# AudioAmp.net
KiCad netlist of a schematic drawn in Altium Designer
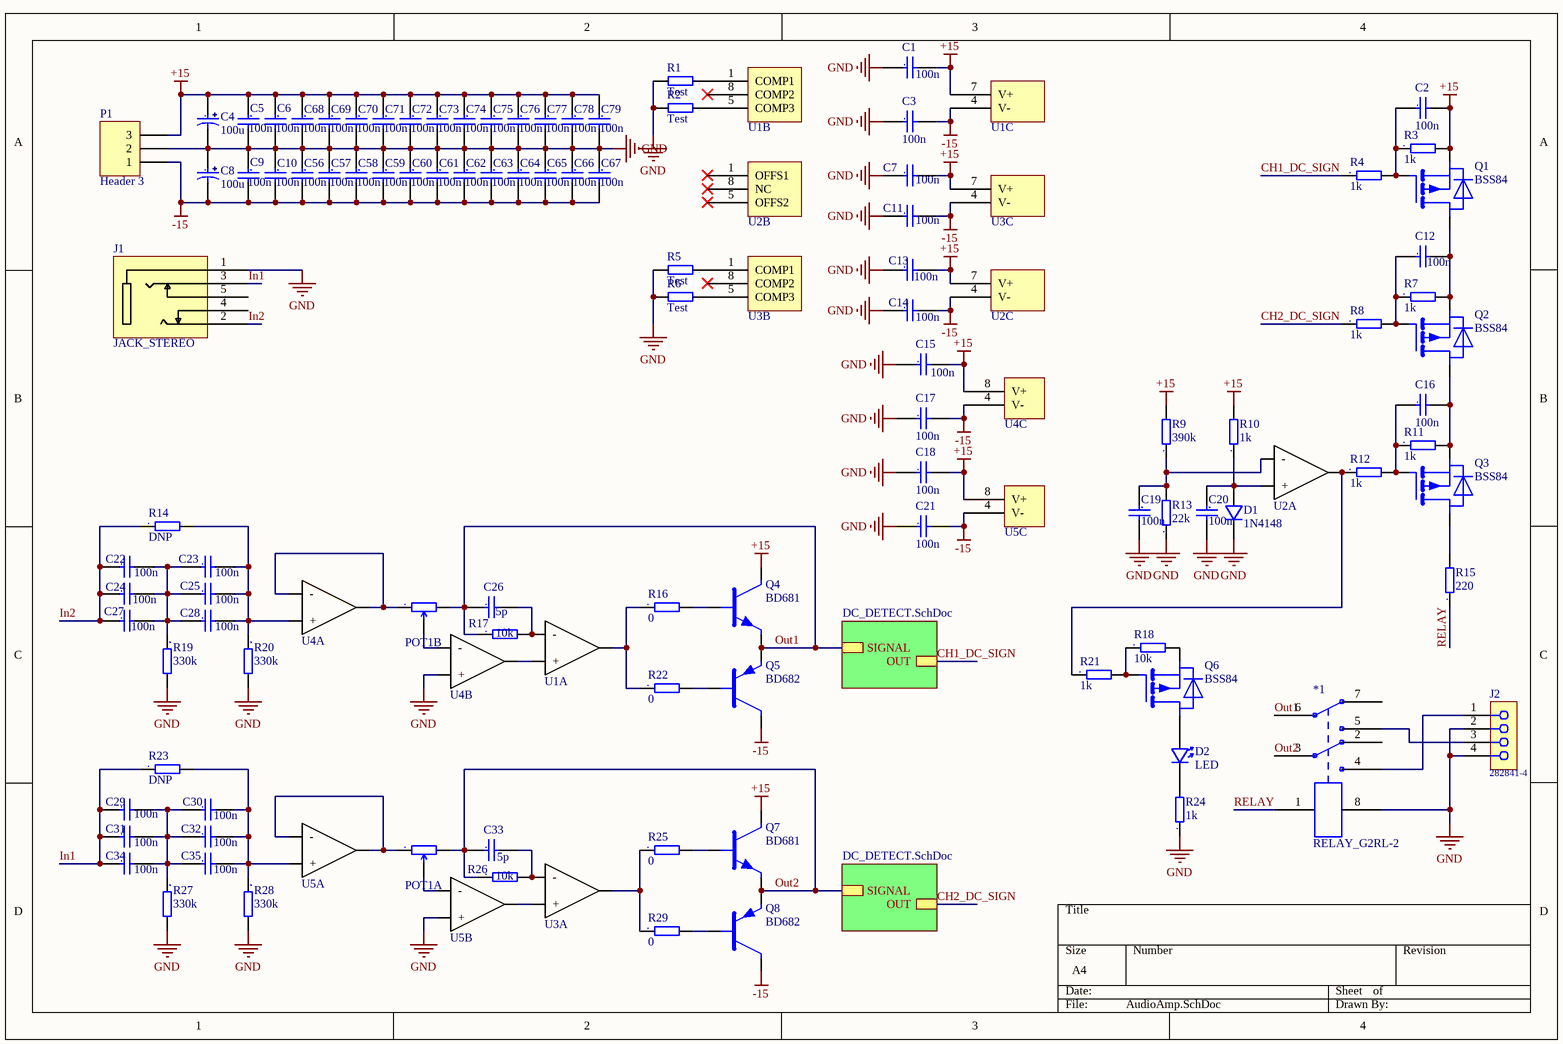
[diagram p0: AudioAmp.SchDoc]

(export (version "E")
  (design (tool "Eeschema 10.0.6"))
  (components
    (comp (ref "*1")
      (value "RELAY_G2RL-2")
      (footprint "G2RL-2")
      (libsource (lib "MyLib") (part "RELAY_G2RL-2"))
    )
    (comp (ref "C1") (value "100n") (footprint "C0603_N") (libsource (lib "MyLib") (part "CAP")))
    (comp (ref "C2") (value "100n") (footprint "C0603_N") (libsource (lib "MyLib") (part "CAP")))
    (comp (ref "C3") (value "100n") (footprint "C0603_N") (libsource (lib "MyLib") (part "CAP")))
    (comp (ref "C4") (value "100u") (footprint "C_TR3D") (libsource (lib "MyLib") (part "CAP_POL")))
    (comp (ref "C5") (value "100n") (footprint "C0603_N") (libsource (lib "MyLib") (part "CAP")))
    (comp (ref "C6") (value "100n") (footprint "C0603_N") (libsource (lib "MyLib") (part "CAP")))
    (comp (ref "C7") (value "100n") (footprint "C0603_N") (libsource (lib "MyLib") (part "CAP")))
    (comp (ref "C8") (value "100u") (footprint "C_TR3D") (libsource (lib "MyLib") (part "CAP_POL")))
    (comp (ref "C9") (value "100n") (footprint "C0603_N") (libsource (lib "MyLib") (part "CAP")))
    (comp (ref "C10") (value "100n") (footprint "C0603_N") (libsource (lib "MyLib") (part "CAP")))
    (comp (ref "C11") (value "100n") (footprint "C0603_N") (libsource (lib "MyLib") (part "CAP")))
    (comp (ref "C12") (value "100n") (footprint "C0603_N") (libsource (lib "MyLib") (part "CAP")))
    (comp (ref "C13") (value "100n") (footprint "C0603_N") (libsource (lib "MyLib") (part "CAP")))
    (comp (ref "C14") (value "100n") (footprint "C0603_N") (libsource (lib "MyLib") (part "CAP")))
    (comp (ref "C15") (value "100n") (footprint "C0603_N") (libsource (lib "MyLib") (part "CAP")))
    (comp (ref "C16") (value "100n") (footprint "C0603_N") (libsource (lib "MyLib") (part "CAP")))
    (comp (ref "C17") (value "100n") (footprint "C0603_N") (libsource (lib "MyLib") (part "CAP")))
    (comp (ref "C18") (value "100n") (footprint "C0603_N") (libsource (lib "MyLib") (part "CAP")))
    (comp (ref "C19") (value "100n") (footprint "C0603_N") (libsource (lib "MyLib") (part "CAP")))
    (comp (ref "C20") (value "100n") (footprint "C0603_N") (libsource (lib "MyLib") (part "CAP")))
    (comp (ref "C21") (value "100n") (footprint "C0603_N") (libsource (lib "MyLib") (part "CAP")))
    (comp (ref "C22") (value "100n") (footprint "C0603_N") (libsource (lib "MyLib") (part "CAP")))
    (comp (ref "C23") (value "100n") (footprint "C0603_N") (libsource (lib "MyLib") (part "CAP")))
    (comp (ref "C24") (value "100n") (footprint "C0603_N") (libsource (lib "MyLib") (part "CAP")))
    (comp (ref "C25") (value "100n") (footprint "C0603_N") (libsource (lib "MyLib") (part "CAP")))
    (comp (ref "C26") (value "5p") (footprint "C0603_N") (libsource (lib "MyLib") (part "CAP")))
    (comp (ref "C27") (value "100n") (footprint "C0603_N") (libsource (lib "MyLib") (part "CAP")))
    (comp (ref "C28") (value "100n") (footprint "C0603_N") (libsource (lib "MyLib") (part "CAP")))
    (comp (ref "C29") (value "100n") (footprint "C0603_N") (libsource (lib "MyLib") (part "CAP")))
    (comp (ref "C30") (value "100n") (footprint "C0603_N") (libsource (lib "MyLib") (part "CAP")))
    (comp (ref "C31") (value "100n") (footprint "C0603_N") (libsource (lib "MyLib") (part "CAP")))
    (comp (ref "C32") (value "100n") (footprint "C0603_N") (libsource (lib "MyLib") (part "CAP")))
    (comp (ref "C33") (value "5p") (footprint "C0603_N") (libsource (lib "MyLib") (part "CAP")))
    (comp (ref "C34") (value "100n") (footprint "C0603_N") (libsource (lib "MyLib") (part "CAP")))
    (comp (ref "C35") (value "100n") (footprint "C0603_N") (libsource (lib "MyLib") (part "CAP")))
    (comp (ref "C56") (value "100n") (footprint "C0603_N") (libsource (lib "MyLib") (part "CAP")))
    (comp (ref "C57") (value "100n") (footprint "C0603_N") (libsource (lib "MyLib") (part "CAP")))
    (comp (ref "C58") (value "100n") (footprint "C0603_N") (libsource (lib "MyLib") (part "CAP")))
    (comp (ref "C59") (value "100n") (footprint "C0603_N") (libsource (lib "MyLib") (part "CAP")))
    (comp (ref "C60") (value "100n") (footprint "C0603_N") (libsource (lib "MyLib") (part "CAP")))
    (comp (ref "C61") (value "100n") (footprint "C0603_N") (libsource (lib "MyLib") (part "CAP")))
    (comp (ref "C62") (value "100n") (footprint "C0603_N") (libsource (lib "MyLib") (part "CAP")))
    (comp (ref "C63") (value "100n") (footprint "C0603_N") (libsource (lib "MyLib") (part "CAP")))
    (comp (ref "C64") (value "100n") (footprint "C0603_N") (libsource (lib "MyLib") (part "CAP")))
    (comp (ref "C65") (value "100n") (footprint "C0603_N") (libsource (lib "MyLib") (part "CAP")))
    (comp (ref "C66") (value "100n") (footprint "C0603_N") (libsource (lib "MyLib") (part "CAP")))
    (comp (ref "C67") (value "100n") (footprint "C0603_N") (libsource (lib "MyLib") (part "CAP")))
    (comp (ref "C68") (value "100n") (footprint "C0603_N") (libsource (lib "MyLib") (part "CAP")))
    (comp (ref "C69") (value "100n") (footprint "C0603_N") (libsource (lib "MyLib") (part "CAP")))
    (comp (ref "C70") (value "100n") (footprint "C0603_N") (libsource (lib "MyLib") (part "CAP")))
    (comp (ref "C71") (value "100n") (footprint "C0603_N") (libsource (lib "MyLib") (part "CAP")))
    (comp (ref "C72") (value "100n") (footprint "C0603_N") (libsource (lib "MyLib") (part "CAP")))
    (comp (ref "C73") (value "100n") (footprint "C0603_N") (libsource (lib "MyLib") (part "CAP")))
    (comp (ref "C74") (value "100n") (footprint "C0603_N") (libsource (lib "MyLib") (part "CAP")))
    (comp (ref "C75") (value "100n") (footprint "C0603_N") (libsource (lib "MyLib") (part "CAP")))
    (comp (ref "C76") (value "100n") (footprint "C0603_N") (libsource (lib "MyLib") (part "CAP")))
    (comp (ref "C77") (value "100n") (footprint "C0603_N") (libsource (lib "MyLib") (part "CAP")))
    (comp (ref "C78") (value "100n") (footprint "C0603_N") (libsource (lib "MyLib") (part "CAP")))
    (comp (ref "C79") (value "100n") (footprint "C0603_N") (libsource (lib "MyLib") (part "CAP")))
    (comp (ref "D1") (value "1N4148") (footprint "SOD-80") (libsource (lib "MyLib") (part "DIODE")))
    (comp (ref "D2") (value "LED") (footprint "LED_3mm") (libsource (lib "MyLib") (part "LED")))
    (comp (ref "J1")
      (value "JACK_STEREO")
      (footprint "1503 09")
      (description "3,5mm Stereo Jack connector, Lumberg 1503 09 type")
      (libsource (lib "MyLib") (part "JACK_STEREO"))
    )
    (comp (ref "J2")
      (value "282841-4")
      (footprint "TERM_BLOCK_4x1")
      (description "Socket")
      (libsource (lib "MyLib") (part "SOCHDR_4X1"))
    )
    (comp (ref "P1")
      (value "Header 3")
      (footprint "HDR1X3")
      (description "Header, 3-Pin")
      (fields (field (name "PUBLISHER") "Altium Limited"))
      (libsource (lib "Miscellaneous Connectors") (part "Header 3"))
    )
    (comp (ref "POT1")
      (value "RES_POT_S")
      (footprint "POT_STEREO")
      (description "Stereo")
      (libsource (lib "MyLib") (part "RES_POT_S"))
    )
    (comp (ref "Q1") (value "BSS84") (footprint "SOT23_123_N") (libsource (lib "MyLib") (part "MOSFET_P")))
    (comp (ref "Q2") (value "BSS84") (footprint "SOT23_123_N") (libsource (lib "MyLib") (part "MOSFET_P")))
    (comp (ref "Q3") (value "BSS84") (footprint "SOT23_123_N") (libsource (lib "MyLib") (part "MOSFET_P")))
    (comp (ref "Q4") (value "BD681") (footprint "TO-126") (libsource (lib "MyLib") (part "BJT_NPN")))
    (comp (ref "Q5") (value "BD682") (footprint "TO-126") (libsource (lib "MyLib") (part "BJT_PNP")))
    (comp (ref "Q6") (value "BSS84") (footprint "SOT23_123_N") (libsource (lib "MyLib") (part "MOSFET_P")))
    (comp (ref "Q7") (value "BD681") (footprint "TO-126") (libsource (lib "MyLib") (part "BJT_NPN")))
    (comp (ref "Q8") (value "BD682") (footprint "TO-126") (libsource (lib "MyLib") (part "BJT_PNP")))
    (comp (ref "R1") (value "Test") (footprint "R0603_N") (libsource (lib "MyLib") (part "RES")))
    (comp (ref "R2") (value "Test") (footprint "R0603_N") (libsource (lib "MyLib") (part "RES")))
    (comp (ref "R3") (value "1k") (footprint "R0603_N") (libsource (lib "MyLib") (part "RES")))
    (comp (ref "R4") (value "1k") (footprint "R0603_N") (libsource (lib "MyLib") (part "RES")))
    (comp (ref "R5") (value "Test") (footprint "R0603_N") (libsource (lib "MyLib") (part "RES")))
    (comp (ref "R6") (value "Test") (footprint "R0603_N") (libsource (lib "MyLib") (part "RES")))
    (comp (ref "R7") (value "1k") (footprint "R0603_N") (libsource (lib "MyLib") (part "RES")))
    (comp (ref "R8") (value "1k") (footprint "R0603_N") (libsource (lib "MyLib") (part "RES")))
    (comp (ref "R9") (value "390k") (footprint "R0603_N") (libsource (lib "MyLib") (part "RES")))
    (comp (ref "R10") (value "1k") (footprint "R0603_N") (libsource (lib "MyLib") (part "RES")))
    (comp (ref "R11") (value "1k") (footprint "R0603_N") (libsource (lib "MyLib") (part "RES")))
    (comp (ref "R12") (value "1k") (footprint "R0603_N") (libsource (lib "MyLib") (part "RES")))
    (comp (ref "R13") (value "22k") (footprint "R0603_N") (libsource (lib "MyLib") (part "RES")))
    (comp (ref "R14") (value "DNP") (footprint "R0603_N") (libsource (lib "MyLib") (part "RES")))
    (comp (ref "R15") (value "220") (footprint "R0603_N") (libsource (lib "MyLib") (part "RES")))
    (comp (ref "R16") (value "0") (footprint "R0603_N") (libsource (lib "MyLib") (part "RES")))
    (comp (ref "R17") (value "10k") (footprint "R0603_N") (libsource (lib "MyLib") (part "RES")))
    (comp (ref "R18") (value "10k") (footprint "R0603_N") (libsource (lib "MyLib") (part "RES")))
    (comp (ref "R19") (value "330k") (footprint "R0603_N") (libsource (lib "MyLib") (part "RES")))
    (comp (ref "R20") (value "330k") (footprint "R0603_N") (libsource (lib "MyLib") (part "RES")))
    (comp (ref "R21") (value "1k") (footprint "R0603_N") (libsource (lib "MyLib") (part "RES")))
    (comp (ref "R22") (value "0") (footprint "R0603_N") (libsource (lib "MyLib") (part "RES")))
    (comp (ref "R23") (value "DNP") (footprint "R0603_N") (libsource (lib "MyLib") (part "RES")))
    (comp (ref "R24") (value "1k") (footprint "R0603_N") (libsource (lib "MyLib") (part "RES")))
    (comp (ref "R25") (value "0") (footprint "R0603_N") (libsource (lib "MyLib") (part "RES")))
    (comp (ref "R26") (value "10k") (footprint "R0603_N") (libsource (lib "MyLib") (part "RES")))
    (comp (ref "R27") (value "330k") (footprint "R0603_N") (libsource (lib "MyLib") (part "RES")))
    (comp (ref "R28") (value "330k") (footprint "R0603_N") (libsource (lib "MyLib") (part "RES")))
    (comp (ref "R29") (value "0") (footprint "R0603_N") (libsource (lib "MyLib") (part "RES")))
    (comp (ref "U1") (value "LM318") (footprint "SOIC-8") (libsource (lib "MyLib") (part "LM318")))
    (comp (ref "U2") (value "uA741") (footprint "SOIC-8") (libsource (lib "MyLib") (part "uA741")))
    (comp (ref "U3") (value "LM318") (footprint "SOIC-8") (libsource (lib "MyLib") (part "LM318")))
    (comp (ref "U4")
      (value "TL072")
      (footprint "SOIC-8")
      (description "Dual op. amp.")
      (libsource (lib "MyLib") (part "TL072"))
    )
    (comp (ref "U5")
      (value "TL072")
      (footprint "SOIC-8")
      (description "Dual op. amp.")
      (libsource (lib "MyLib") (part "TL072"))
    )
  )
  (nets
    (net (code "1") (name "+15") (class "Default")
      (node (ref "C1") (pin "2") (pinfunction "2_2") (pintype "passive"))
      (node (ref "C13") (pin "2") (pinfunction "2_2") (pintype "passive"))
      (node (ref "C15") (pin "2") (pinfunction "2_2") (pintype "passive"))
      (node (ref "C18") (pin "2") (pinfunction "2_2") (pintype "passive"))
      (node (ref "C2") (pin "2") (pinfunction "2_2") (pintype "passive"))
      (node (ref "C4") (pin "P") (pinfunction "P_P") (pintype "passive"))
      (node (ref "C5") (pin "1") (pinfunction "1_1") (pintype "passive"))
      (node (ref "C6") (pin "1") (pinfunction "1_1") (pintype "passive"))
      (node (ref "C68") (pin "1") (pinfunction "1_1") (pintype "passive"))
      (node (ref "C69") (pin "1") (pinfunction "1_1") (pintype "passive"))
      (node (ref "C7") (pin "2") (pinfunction "2_2") (pintype "passive"))
      (node (ref "C70") (pin "1") (pinfunction "1_1") (pintype "passive"))
      (node (ref "C71") (pin "1") (pinfunction "1_1") (pintype "passive"))
      (node (ref "C72") (pin "1") (pinfunction "1_1") (pintype "passive"))
      (node (ref "C73") (pin "1") (pinfunction "1_1") (pintype "passive"))
      (node (ref "C74") (pin "1") (pinfunction "1_1") (pintype "passive"))
      (node (ref "C75") (pin "1") (pinfunction "1_1") (pintype "passive"))
      (node (ref "C76") (pin "1") (pinfunction "1_1") (pintype "passive"))
      (node (ref "C77") (pin "1") (pinfunction "1_1") (pintype "passive"))
      (node (ref "C78") (pin "1") (pinfunction "1_1") (pintype "passive"))
      (node (ref "C79") (pin "1") (pinfunction "1_1") (pintype "passive"))
      (node (ref "P1") (pin "3") (pinfunction "3_3") (pintype "passive"))
      (node (ref "Q1") (pin "S") (pinfunction "S_S") (pintype "passive"))
      (node (ref "Q4") (pin "C") (pinfunction "C_C") (pintype "passive"))
      (node (ref "Q7") (pin "C") (pinfunction "C_C") (pintype "passive"))
      (node (ref "R10") (pin "2") (pinfunction "2_2") (pintype "passive"))
      (node (ref "R3") (pin "2") (pinfunction "2_2") (pintype "passive"))
      (node (ref "R9") (pin "2") (pinfunction "2_2") (pintype "passive"))
      (node (ref "U1") (pin "7") (pinfunction "V+_7") (pintype "passive"))
      (node (ref "U2") (pin "7") (pinfunction "V+_7") (pintype "passive"))
      (node (ref "U3") (pin "7") (pinfunction "V+_7") (pintype "passive"))
      (node (ref "U4") (pin "8") (pinfunction "V+_8") (pintype "passive"))
      (node (ref "U5") (pin "8") (pinfunction "V+_8") (pintype "passive"))
    )
    (net (code "2") (name "-15") (class "Default")
      (node (ref "C10") (pin "2") (pinfunction "2_2") (pintype "passive"))
      (node (ref "C11") (pin "2") (pinfunction "2_2") (pintype "passive"))
      (node (ref "C14") (pin "2") (pinfunction "2_2") (pintype "passive"))
      (node (ref "C17") (pin "2") (pinfunction "2_2") (pintype "passive"))
      (node (ref "C21") (pin "2") (pinfunction "2_2") (pintype "passive"))
      (node (ref "C3") (pin "2") (pinfunction "2_2") (pintype "passive"))
      (node (ref "C56") (pin "2") (pinfunction "2_2") (pintype "passive"))
      (node (ref "C57") (pin "2") (pinfunction "2_2") (pintype "passive"))
      (node (ref "C58") (pin "2") (pinfunction "2_2") (pintype "passive"))
      (node (ref "C59") (pin "2") (pinfunction "2_2") (pintype "passive"))
      (node (ref "C60") (pin "2") (pinfunction "2_2") (pintype "passive"))
      (node (ref "C61") (pin "2") (pinfunction "2_2") (pintype "passive"))
      (node (ref "C62") (pin "2") (pinfunction "2_2") (pintype "passive"))
      (node (ref "C63") (pin "2") (pinfunction "2_2") (pintype "passive"))
      (node (ref "C64") (pin "2") (pinfunction "2_2") (pintype "passive"))
      (node (ref "C65") (pin "2") (pinfunction "2_2") (pintype "passive"))
      (node (ref "C66") (pin "2") (pinfunction "2_2") (pintype "passive"))
      (node (ref "C67") (pin "2") (pinfunction "2_2") (pintype "passive"))
      (node (ref "C8") (pin "N") (pinfunction "N_N") (pintype "passive"))
      (node (ref "C9") (pin "2") (pinfunction "2_2") (pintype "passive"))
      (node (ref "P1") (pin "1") (pinfunction "1_1") (pintype "passive"))
      (node (ref "Q5") (pin "C") (pinfunction "C_C") (pintype "passive"))
      (node (ref "Q8") (pin "C") (pinfunction "C_C") (pintype "passive"))
      (node (ref "U1") (pin "4") (pinfunction "V-_4") (pintype "passive"))
      (node (ref "U2") (pin "4") (pinfunction "V-_4") (pintype "passive"))
      (node (ref "U3") (pin "4") (pinfunction "V-_4") (pintype "passive"))
      (node (ref "U4") (pin "4") (pinfunction "V-_4") (pintype "passive"))
      (node (ref "U5") (pin "4") (pinfunction "V-_4") (pintype "passive"))
    )
    (net (code "3") (name "/CH1_DC_SIGN") (class "Default")
      (node (ref "R4") (pin "1") (pinfunction "1_1") (pintype "passive"))
    )
    (net (code "4") (name "/CH2_DC_SIGN") (class "Default")
      (node (ref "R8") (pin "1") (pinfunction "1_1") (pintype "passive"))
    )
    (net (code "5") (name "/In1") (class "Default")
      (node (ref "C29") (pin "1") (pinfunction "1_1") (pintype "passive"))
      (node (ref "C31") (pin "1") (pinfunction "1_1") (pintype "passive"))
      (node (ref "C34") (pin "1") (pinfunction "1_1") (pintype "passive"))
      (node (ref "J1") (pin "3") (pintype "passive"))
      (node (ref "R23") (pin "1") (pinfunction "1_1") (pintype "passive"))
    )
    (net (code "6") (name "/In2") (class "Default")
      (node (ref "C22") (pin "1") (pinfunction "1_1") (pintype "passive"))
      (node (ref "C24") (pin "1") (pinfunction "1_1") (pintype "passive"))
      (node (ref "C27") (pin "1") (pinfunction "1_1") (pintype "passive"))
      (node (ref "J1") (pin "2") (pintype "passive"))
      (node (ref "R14") (pin "1") (pinfunction "1_1") (pintype "passive"))
    )
    (net (code "7") (name "/Out1") (class "Default")
      (node (ref "*1") (pin "6") (pintype "passive"))
      (node (ref "C26") (pin "1") (pinfunction "1_1") (pintype "passive"))
      (node (ref "POT1") (pin "6") (pinfunction "CW_6") (pintype "passive"))
      (node (ref "Q4") (pin "E") (pinfunction "E_E") (pintype "passive"))
      (node (ref "Q5") (pin "E") (pinfunction "E_E") (pintype "passive"))
      (node (ref "R17") (pin "1") (pinfunction "1_1") (pintype "passive"))
    )
    (net (code "8") (name "/Out2") (class "Default")
      (node (ref "*1") (pin "3") (pintype "passive"))
      (node (ref "C33") (pin "1") (pinfunction "1_1") (pintype "passive"))
      (node (ref "POT1") (pin "3") (pinfunction "CW_3") (pintype "passive"))
      (node (ref "Q7") (pin "E") (pinfunction "E_E") (pintype "passive"))
      (node (ref "Q8") (pin "E") (pinfunction "E_E") (pintype "passive"))
      (node (ref "R26") (pin "1") (pinfunction "1_1") (pintype "passive"))
    )
    (net (code "9") (name "/RELAY") (class "Default")
      (node (ref "*1") (pin "1") (pintype "passive"))
      (node (ref "R15") (pin "1") (pinfunction "1_1") (pintype "passive"))
    )
    (net (code "10") (name "GND") (class "Default")
      (node (ref "*1") (pin "8") (pintype "passive"))
      (node (ref "C1") (pin "1") (pinfunction "1_1") (pintype "passive"))
      (node (ref "C10") (pin "1") (pinfunction "1_1") (pintype "passive"))
      (node (ref "C11") (pin "1") (pinfunction "1_1") (pintype "passive"))
      (node (ref "C13") (pin "1") (pinfunction "1_1") (pintype "passive"))
      (node (ref "C14") (pin "1") (pinfunction "1_1") (pintype "passive"))
      (node (ref "C15") (pin "1") (pinfunction "1_1") (pintype "passive"))
      (node (ref "C17") (pin "1") (pinfunction "1_1") (pintype "passive"))
      (node (ref "C18") (pin "1") (pinfunction "1_1") (pintype "passive"))
      (node (ref "C19") (pin "2") (pinfunction "2_2") (pintype "passive"))
      (node (ref "C20") (pin "2") (pinfunction "2_2") (pintype "passive"))
      (node (ref "C21") (pin "1") (pinfunction "1_1") (pintype "passive"))
      (node (ref "C3") (pin "1") (pinfunction "1_1") (pintype "passive"))
      (node (ref "C4") (pin "N") (pinfunction "N_N") (pintype "passive"))
      (node (ref "C5") (pin "2") (pinfunction "2_2") (pintype "passive"))
      (node (ref "C56") (pin "1") (pinfunction "1_1") (pintype "passive"))
      (node (ref "C57") (pin "1") (pinfunction "1_1") (pintype "passive"))
      (node (ref "C58") (pin "1") (pinfunction "1_1") (pintype "passive"))
      (node (ref "C59") (pin "1") (pinfunction "1_1") (pintype "passive"))
      (node (ref "C6") (pin "2") (pinfunction "2_2") (pintype "passive"))
      (node (ref "C60") (pin "1") (pinfunction "1_1") (pintype "passive"))
      (node (ref "C61") (pin "1") (pinfunction "1_1") (pintype "passive"))
      (node (ref "C62") (pin "1") (pinfunction "1_1") (pintype "passive"))
      (node (ref "C63") (pin "1") (pinfunction "1_1") (pintype "passive"))
      (node (ref "C64") (pin "1") (pinfunction "1_1") (pintype "passive"))
      (node (ref "C65") (pin "1") (pinfunction "1_1") (pintype "passive"))
      (node (ref "C66") (pin "1") (pinfunction "1_1") (pintype "passive"))
      (node (ref "C67") (pin "1") (pinfunction "1_1") (pintype "passive"))
      (node (ref "C68") (pin "2") (pinfunction "2_2") (pintype "passive"))
      (node (ref "C69") (pin "2") (pinfunction "2_2") (pintype "passive"))
      (node (ref "C7") (pin "1") (pinfunction "1_1") (pintype "passive"))
      (node (ref "C70") (pin "2") (pinfunction "2_2") (pintype "passive"))
      (node (ref "C71") (pin "2") (pinfunction "2_2") (pintype "passive"))
      (node (ref "C72") (pin "2") (pinfunction "2_2") (pintype "passive"))
      (node (ref "C73") (pin "2") (pinfunction "2_2") (pintype "passive"))
      (node (ref "C74") (pin "2") (pinfunction "2_2") (pintype "passive"))
      (node (ref "C75") (pin "2") (pinfunction "2_2") (pintype "passive"))
      (node (ref "C76") (pin "2") (pinfunction "2_2") (pintype "passive"))
      (node (ref "C77") (pin "2") (pinfunction "2_2") (pintype "passive"))
      (node (ref "C78") (pin "2") (pinfunction "2_2") (pintype "passive"))
      (node (ref "C79") (pin "2") (pinfunction "2_2") (pintype "passive"))
      (node (ref "C8") (pin "P") (pinfunction "P_P") (pintype "passive"))
      (node (ref "C9") (pin "1") (pinfunction "1_1") (pintype "passive"))
      (node (ref "D1") (pin "C") (pinfunction "C_C") (pintype "passive"))
      (node (ref "J1") (pin "1") (pintype "passive"))
      (node (ref "J2") (pin "2") (pinfunction "2_2") (pintype "passive"))
      (node (ref "J2") (pin "4") (pinfunction "4_4") (pintype "passive"))
      (node (ref "P1") (pin "2") (pinfunction "2_2") (pintype "passive"))
      (node (ref "R1") (pin "2") (pinfunction "2_2") (pintype "passive"))
      (node (ref "R13") (pin "1") (pinfunction "1_1") (pintype "passive"))
      (node (ref "R19") (pin "2") (pinfunction "2_2") (pintype "passive"))
      (node (ref "R2") (pin "2") (pinfunction "2_2") (pintype "passive"))
      (node (ref "R20") (pin "2") (pinfunction "2_2") (pintype "passive"))
      (node (ref "R24") (pin "1") (pinfunction "1_1") (pintype "passive"))
      (node (ref "R27") (pin "2") (pinfunction "2_2") (pintype "passive"))
      (node (ref "R28") (pin "2") (pinfunction "2_2") (pintype "passive"))
      (node (ref "R5") (pin "2") (pinfunction "2_2") (pintype "passive"))
      (node (ref "R6") (pin "2") (pinfunction "2_2") (pintype "passive"))
      (node (ref "U4") (pin "5") (pinfunction "+_5") (pintype "passive"))
      (node (ref "U5") (pin "5") (pinfunction "+_5") (pintype "passive"))
    )
    (net (code "11") (name "Net-(*1-Pad4)") (class "Default")
      (node (ref "*1") (pin "4") (pintype "passive"))
      (node (ref "J2") (pin "1") (pinfunction "1_1") (pintype "passive"))
    )
    (net (code "12") (name "Net-(*1-Pad5)") (class "Default")
      (node (ref "*1") (pin "5") (pintype "passive"))
      (node (ref "J2") (pin "3") (pinfunction "3_3") (pintype "passive"))
    )
    (net (code "13") (name "Net-(C2-Pad1)") (class "Default")
      (node (ref "C2") (pin "1") (pinfunction "1_1") (pintype "passive"))
      (node (ref "Q1") (pin "G") (pinfunction "G_G") (pintype "passive"))
      (node (ref "R3") (pin "1") (pinfunction "1_1") (pintype "passive"))
      (node (ref "R4") (pin "2") (pinfunction "2_2") (pintype "passive"))
    )
    (net (code "14") (name "Net-(C12-Pad1)") (class "Default")
      (node (ref "C12") (pin "1") (pinfunction "1_1") (pintype "passive"))
      (node (ref "Q2") (pin "G") (pinfunction "G_G") (pintype "passive"))
      (node (ref "R7") (pin "1") (pinfunction "1_1") (pintype "passive"))
      (node (ref "R8") (pin "2") (pinfunction "2_2") (pintype "passive"))
    )
    (net (code "15") (name "Net-(C12-Pad2)") (class "Default")
      (node (ref "C12") (pin "2") (pinfunction "2_2") (pintype "passive"))
      (node (ref "Q1") (pin "D") (pinfunction "D_D") (pintype "passive"))
      (node (ref "Q2") (pin "S") (pinfunction "S_S") (pintype "passive"))
      (node (ref "R7") (pin "2") (pinfunction "2_2") (pintype "passive"))
    )
    (net (code "16") (name "Net-(C16-Pad1)") (class "Default")
      (node (ref "C16") (pin "1") (pinfunction "1_1") (pintype "passive"))
      (node (ref "Q3") (pin "G") (pinfunction "G_G") (pintype "passive"))
      (node (ref "R11") (pin "1") (pinfunction "1_1") (pintype "passive"))
      (node (ref "R12") (pin "2") (pinfunction "2_2") (pintype "passive"))
    )
    (net (code "17") (name "Net-(C16-Pad2)") (class "Default")
      (node (ref "C16") (pin "2") (pinfunction "2_2") (pintype "passive"))
      (node (ref "Q2") (pin "D") (pinfunction "D_D") (pintype "passive"))
      (node (ref "Q3") (pin "S") (pinfunction "S_S") (pintype "passive"))
      (node (ref "R11") (pin "2") (pinfunction "2_2") (pintype "passive"))
    )
    (net (code "18") (name "Net-(C22-Pad2)") (class "Default")
      (node (ref "C22") (pin "2") (pinfunction "2_2") (pintype "passive"))
      (node (ref "C23") (pin "1") (pinfunction "1_1") (pintype "passive"))
      (node (ref "C24") (pin "2") (pinfunction "2_2") (pintype "passive"))
      (node (ref "C25") (pin "1") (pinfunction "1_1") (pintype "passive"))
      (node (ref "C27") (pin "2") (pinfunction "2_2") (pintype "passive"))
      (node (ref "C28") (pin "1") (pinfunction "1_1") (pintype "passive"))
      (node (ref "R19") (pin "1") (pinfunction "1_1") (pintype "passive"))
    )
    (net (code "19") (name "Net-(C29-Pad2)") (class "Default")
      (node (ref "C29") (pin "2") (pinfunction "2_2") (pintype "passive"))
      (node (ref "C30") (pin "1") (pinfunction "1_1") (pintype "passive"))
      (node (ref "C31") (pin "2") (pinfunction "2_2") (pintype "passive"))
      (node (ref "C32") (pin "1") (pinfunction "1_1") (pintype "passive"))
      (node (ref "C34") (pin "2") (pinfunction "2_2") (pintype "passive"))
      (node (ref "C35") (pin "1") (pinfunction "1_1") (pintype "passive"))
      (node (ref "R27") (pin "1") (pinfunction "1_1") (pintype "passive"))
    )
    (net (code "20") (name "Net-(D2-PadA)") (class "Default")
      (node (ref "D2") (pin "A") (pinfunction "A_A") (pintype "passive"))
      (node (ref "Q6") (pin "D") (pinfunction "D_D") (pintype "passive"))
    )
    (net (code "21") (name "Net-(D2-PadK)") (class "Default")
      (node (ref "D2") (pin "K") (pinfunction "K_K") (pintype "passive"))
      (node (ref "R24") (pin "2") (pinfunction "2_2") (pintype "passive"))
    )
    (net (code "22") (name "Net-(POT1A-CCW)") (class "Default")
      (node (ref "POT1") (pin "1") (pinfunction "CCW_1") (pintype "passive"))
      (node (ref "U5") (pin "1") (pinfunction "Out_1") (pintype "passive"))
      (node (ref "U5") (pin "2") (pinfunction "-_2") (pintype "passive"))
    )
    (net (code "23") (name "Net-(POT1A-WIPER)") (class "Default")
      (node (ref "POT1") (pin "2") (pinfunction "WIPER_2") (pintype "passive"))
      (node (ref "U5") (pin "6") (pinfunction "-_6") (pintype "passive"))
    )
    (net (code "24") (name "Net-(POT1B-CCW)") (class "Default")
      (node (ref "POT1") (pin "4") (pinfunction "CCW_4") (pintype "passive"))
      (node (ref "U4") (pin "1") (pinfunction "Out_1") (pintype "passive"))
      (node (ref "U4") (pin "2") (pinfunction "-_2") (pintype "passive"))
    )
    (net (code "25") (name "Net-(POT1B-WIPER)") (class "Default")
      (node (ref "POT1") (pin "5") (pinfunction "WIPER_5") (pintype "passive"))
      (node (ref "U4") (pin "6") (pinfunction "-_6") (pintype "passive"))
    )
    (net (code "26") (name "Net-(Q3-PadD)") (class "Default")
      (node (ref "Q3") (pin "D") (pinfunction "D_D") (pintype "passive"))
      (node (ref "R15") (pin "2") (pinfunction "2_2") (pintype "passive"))
    )
    (net (code "27") (name "Net-(Q4-PadB)") (class "Default")
      (node (ref "Q4") (pin "B") (pinfunction "B_B") (pintype "passive"))
      (node (ref "R16") (pin "2") (pinfunction "2_2") (pintype "passive"))
    )
    (net (code "28") (name "Net-(Q5-PadB)") (class "Default")
      (node (ref "Q5") (pin "B") (pinfunction "B_B") (pintype "passive"))
      (node (ref "R22") (pin "2") (pinfunction "2_2") (pintype "passive"))
    )
    (net (code "29") (name "Net-(Q6-PadG)") (class "Default")
      (node (ref "Q6") (pin "G") (pinfunction "G_G") (pintype "passive"))
      (node (ref "R18") (pin "1") (pinfunction "1_1") (pintype "passive"))
      (node (ref "R21") (pin "2") (pinfunction "2_2") (pintype "passive"))
    )
    (net (code "30") (name "Net-(Q6-PadS)") (class "Default")
      (node (ref "Q6") (pin "S") (pinfunction "S_S") (pintype "passive"))
      (node (ref "R18") (pin "2") (pinfunction "2_2") (pintype "passive"))
    )
    (net (code "31") (name "Net-(Q7-PadB)") (class "Default")
      (node (ref "Q7") (pin "B") (pinfunction "B_B") (pintype "passive"))
      (node (ref "R25") (pin "2") (pinfunction "2_2") (pintype "passive"))
    )
    (net (code "32") (name "Net-(Q8-PadB)") (class "Default")
      (node (ref "Q8") (pin "B") (pinfunction "B_B") (pintype "passive"))
      (node (ref "R29") (pin "2") (pinfunction "2_2") (pintype "passive"))
    )
    (net (code "33") (name "Net-(U1A-+)") (class "Default")
      (node (ref "U1") (pin "3") (pinfunction "+_3") (pintype "passive"))
      (node (ref "U4") (pin "7") (pinfunction "Out_7") (pintype "passive"))
    )
    (net (code "34") (name "Net-(U1A--)") (class "Default")
      (node (ref "C26") (pin "2") (pinfunction "2_2") (pintype "passive"))
      (node (ref "R17") (pin "2") (pinfunction "2_2") (pintype "passive"))
      (node (ref "U1") (pin "2") (pinfunction "-_2") (pintype "passive"))
    )
    (net (code "35") (name "Net-(U1A-Out)") (class "Default")
      (node (ref "R16") (pin "1") (pinfunction "1_1") (pintype "passive"))
      (node (ref "R22") (pin "1") (pinfunction "1_1") (pintype "passive"))
      (node (ref "U1") (pin "6") (pinfunction "Out_6") (pintype "passive"))
    )
    (net (code "36") (name "Net-(U1B-COMP1)") (class "Default")
      (node (ref "R1") (pin "1") (pinfunction "1_1") (pintype "passive"))
      (node (ref "U1") (pin "1") (pinfunction "COMP1_1") (pintype "passive"))
    )
    (net (code "37") (name "Net-(U1B-COMP3)") (class "Default")
      (node (ref "R2") (pin "1") (pinfunction "1_1") (pintype "passive"))
      (node (ref "U1") (pin "5") (pinfunction "COMP3_5") (pintype "passive"))
    )
    (net (code "38") (name "Net-(U2A-+)") (class "Default")
      (node (ref "C20") (pin "1") (pinfunction "1_1") (pintype "passive"))
      (node (ref "D1") (pin "A") (pinfunction "A_A") (pintype "passive"))
      (node (ref "R10") (pin "1") (pinfunction "1_1") (pintype "passive"))
      (node (ref "U2") (pin "3") (pinfunction "+_3") (pintype "passive"))
    )
    (net (code "39") (name "Net-(U2A--)") (class "Default")
      (node (ref "C19") (pin "1") (pinfunction "1_1") (pintype "passive"))
      (node (ref "R13") (pin "2") (pinfunction "2_2") (pintype "passive"))
      (node (ref "R9") (pin "1") (pinfunction "1_1") (pintype "passive"))
      (node (ref "U2") (pin "2") (pinfunction "-_2") (pintype "passive"))
    )
    (net (code "40") (name "Net-(U2A-Out)") (class "Default")
      (node (ref "R12") (pin "1") (pinfunction "1_1") (pintype "passive"))
      (node (ref "R21") (pin "1") (pinfunction "1_1") (pintype "passive"))
      (node (ref "U2") (pin "6") (pinfunction "Out_6") (pintype "passive"))
    )
    (net (code "41") (name "Net-(U3A-+)") (class "Default")
      (node (ref "U3") (pin "3") (pinfunction "+_3") (pintype "passive"))
      (node (ref "U5") (pin "7") (pinfunction "Out_7") (pintype "passive"))
    )
    (net (code "42") (name "Net-(U3A--)") (class "Default")
      (node (ref "C33") (pin "2") (pinfunction "2_2") (pintype "passive"))
      (node (ref "R26") (pin "2") (pinfunction "2_2") (pintype "passive"))
      (node (ref "U3") (pin "2") (pinfunction "-_2") (pintype "passive"))
    )
    (net (code "43") (name "Net-(U3A-Out)") (class "Default")
      (node (ref "R25") (pin "1") (pinfunction "1_1") (pintype "passive"))
      (node (ref "R29") (pin "1") (pinfunction "1_1") (pintype "passive"))
      (node (ref "U3") (pin "6") (pinfunction "Out_6") (pintype "passive"))
    )
    (net (code "44") (name "Net-(U3B-COMP1)") (class "Default")
      (node (ref "R5") (pin "1") (pinfunction "1_1") (pintype "passive"))
      (node (ref "U3") (pin "1") (pinfunction "COMP1_1") (pintype "passive"))
    )
    (net (code "45") (name "Net-(U3B-COMP3)") (class "Default")
      (node (ref "R6") (pin "1") (pinfunction "1_1") (pintype "passive"))
      (node (ref "U3") (pin "5") (pinfunction "COMP3_5") (pintype "passive"))
    )
    (net (code "46") (name "Net-(U4A-+)") (class "Default")
      (node (ref "C23") (pin "2") (pinfunction "2_2") (pintype "passive"))
      (node (ref "C25") (pin "2") (pinfunction "2_2") (pintype "passive"))
      (node (ref "C28") (pin "2") (pinfunction "2_2") (pintype "passive"))
      (node (ref "R14") (pin "2") (pinfunction "2_2") (pintype "passive"))
      (node (ref "R20") (pin "1") (pinfunction "1_1") (pintype "passive"))
      (node (ref "U4") (pin "3") (pinfunction "+_3") (pintype "passive"))
    )
    (net (code "47") (name "Net-(U5A-+)") (class "Default")
      (node (ref "C30") (pin "2") (pinfunction "2_2") (pintype "passive"))
      (node (ref "C32") (pin "2") (pinfunction "2_2") (pintype "passive"))
      (node (ref "C35") (pin "2") (pinfunction "2_2") (pintype "passive"))
      (node (ref "R23") (pin "2") (pinfunction "2_2") (pintype "passive"))
      (node (ref "R28") (pin "1") (pinfunction "1_1") (pintype "passive"))
      (node (ref "U5") (pin "3") (pinfunction "+_3") (pintype "passive"))
    )
    (net (code "48") (name "unconnected-(*1-Pad2)") (class "Default")
      (node (ref "*1") (pin "2") (pintype "passive"))
    )
    (net (code "49") (name "unconnected-(*1-Pad7)") (class "Default")
      (node (ref "*1") (pin "7") (pintype "passive"))
    )
    (net (code "50") (name "unconnected-(J1-Pad4)") (class "Default")
      (node (ref "J1") (pin "4") (pintype "passive"))
    )
    (net (code "51") (name "unconnected-(J1-Pad5)") (class "Default")
      (node (ref "J1") (pin "5") (pintype "passive"))
    )
    (net (code "52") (name "unconnected-(U1B-COMP2-Pad8)") (class "Default")
      (node (ref "U1") (pin "8") (pinfunction "COMP2_8") (pintype "passive+no_connect"))
    )
    (net (code "53") (name "unconnected-(U2B-NC-Pad8)") (class "Default")
      (node (ref "U2") (pin "8") (pinfunction "NC_8") (pintype "passive+no_connect"))
    )
    (net (code "54") (name "unconnected-(U2B-OFFS1-Pad1)") (class "Default")
      (node (ref "U2") (pin "1") (pinfunction "OFFS1_1") (pintype "passive+no_connect"))
    )
    (net (code "55") (name "unconnected-(U2B-OFFS2-Pad5)") (class "Default")
      (node (ref "U2") (pin "5") (pinfunction "OFFS2_5") (pintype "passive+no_connect"))
    )
    (net (code "56") (name "unconnected-(U3B-COMP2-Pad8)") (class "Default")
      (node (ref "U3") (pin "8") (pinfunction "COMP2_8") (pintype "passive+no_connect"))
    )
  )
)
